# Adafruit_ADG729_Dual_1-to-4_Analog_Switc.net
KiCad netlist of a schematic drawn in EAGLE
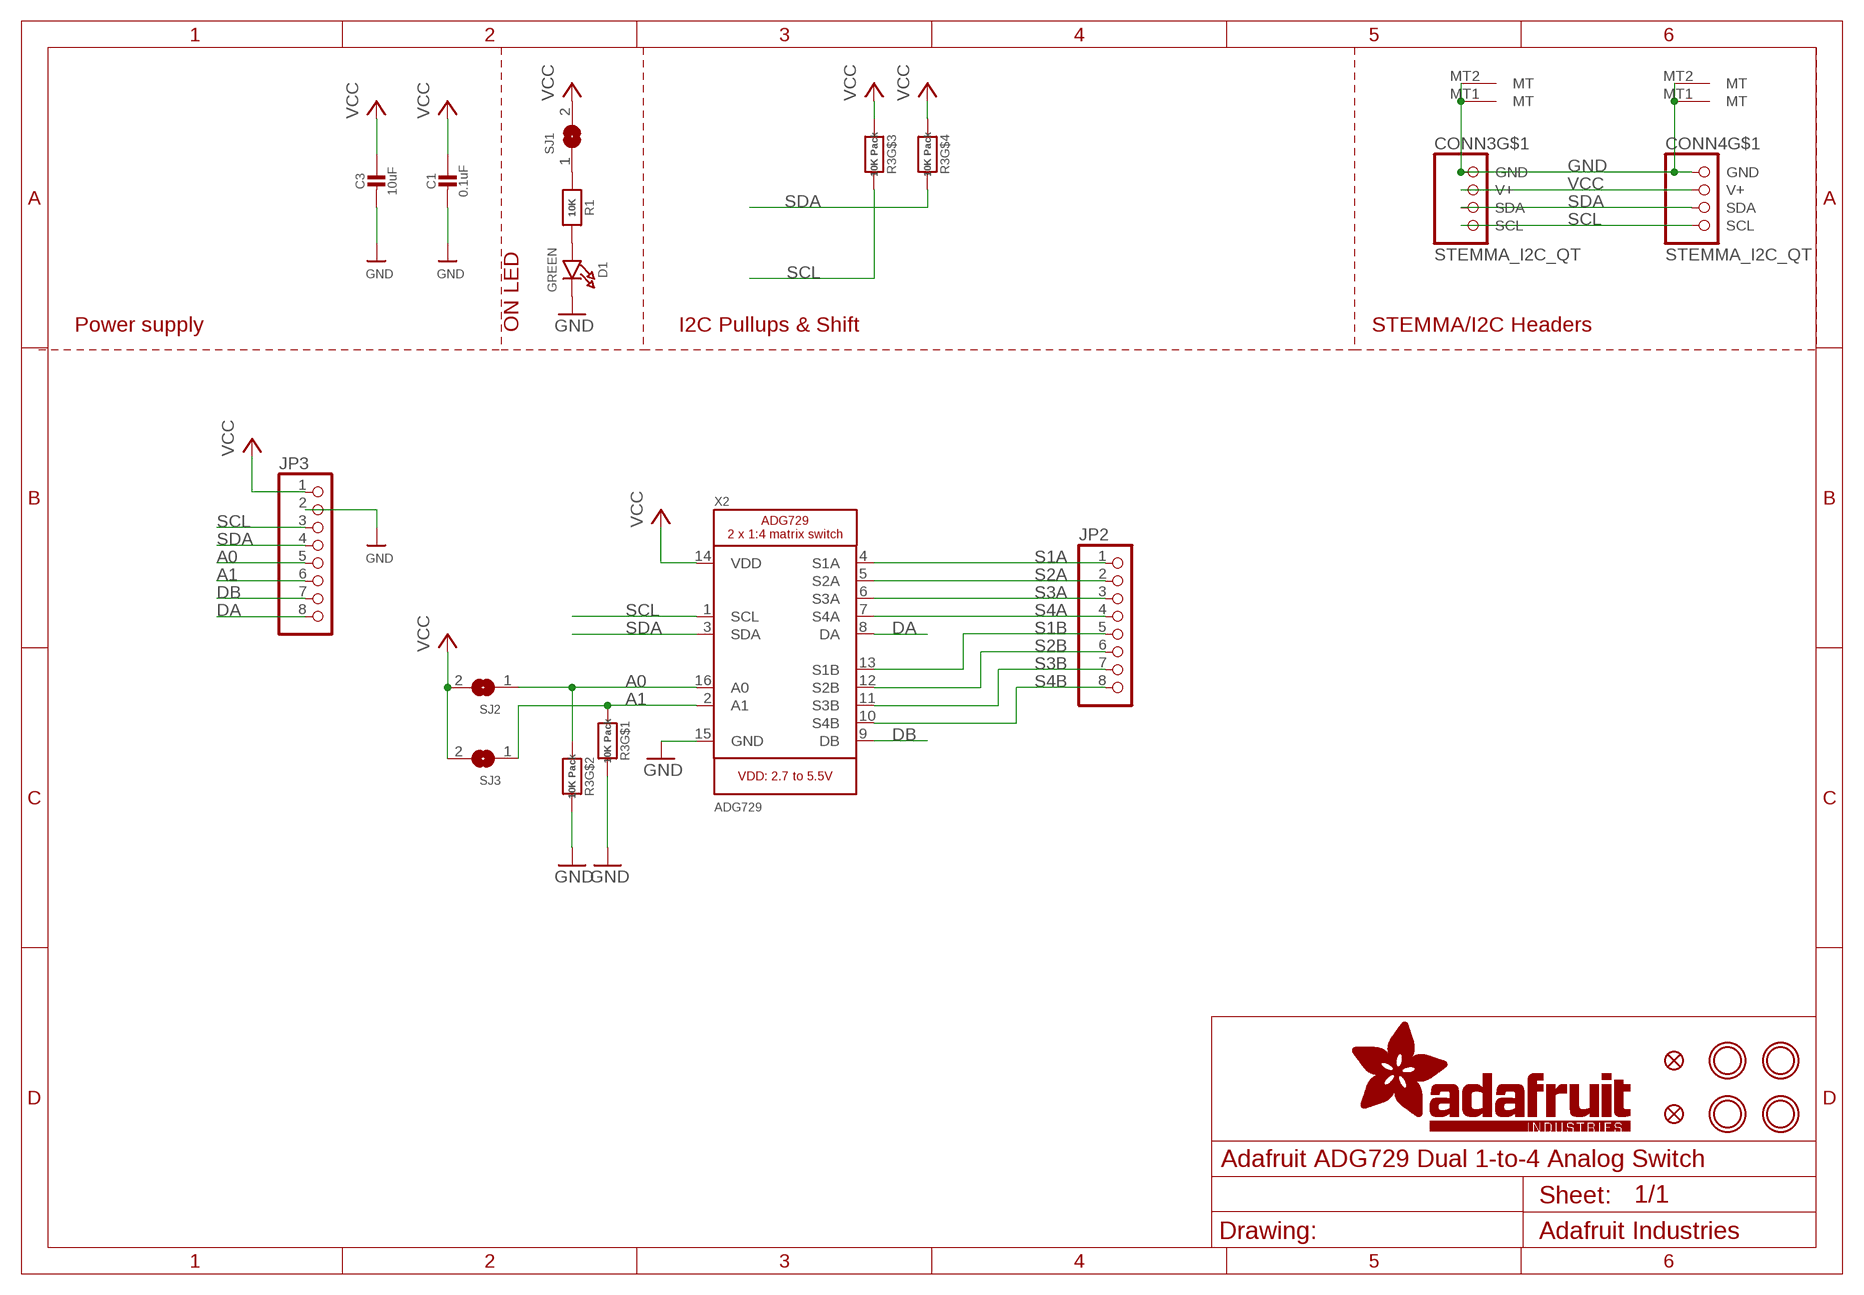
[diagram p0: schematic, sheet 1]

(export (version "E")
  (design (tool "Eeschema 10.0.6"))
  (components
    (comp (ref "C1")
      (value "0.1uF")
      (footprint "eagle-import:0603-NO")
      (libsource (lib "eagle-import") (part "CAP_CERAMIC0603_NO"))
    )
    (comp (ref "C3")
      (value "10uF")
      (footprint "eagle-import:0805-NO")
      (libsource (lib "eagle-import") (part "CAP_CERAMIC0805-NOOUTLINE"))
    )
    (comp (ref "CONN3")
      (value "STEMMA_I2C_QT")
      (footprint "eagle-import:JST_SH4")
      (libsource (lib "eagle-import") (part "STEMMA_I2C_QT"))
    )
    (comp (ref "CONN4")
      (value "STEMMA_I2C_QT")
      (footprint "eagle-import:JST_SH4")
      (libsource (lib "eagle-import") (part "STEMMA_I2C_QT"))
    )
    (comp (ref "D1")
      (value "GREEN")
      (footprint "eagle-import:CHIPLED_0603_NOOUTLINE")
      (libsource (lib "eagle-import") (part "LED0603_NOOUTLINE"))
    )
    (comp (ref "FID3")
      (value "FIDUCIAL_1MM")
      (footprint "eagle-import:FIDUCIAL_1MM")
      (libsource (lib "eagle-import") (part "FIDUCIAL_1MM"))
    )
    (comp (ref "FID4")
      (value "FIDUCIAL_1MM")
      (footprint "eagle-import:FIDUCIAL_1MM")
      (libsource (lib "eagle-import") (part "FIDUCIAL_1MM"))
    )
    (comp (ref "JP2")
      (value "HEADER-1X870MIL")
      (footprint "eagle-import:1X08_ROUND_70")
      (libsource (lib "eagle-import") (part "HEADER-1X870MIL"))
    )
    (comp (ref "JP3")
      (value "HEADER-1X870MIL")
      (footprint "eagle-import:1X08_ROUND_70")
      (libsource (lib "eagle-import") (part "HEADER-1X870MIL"))
    )
    (comp (ref "R1")
      (value "10K")
      (footprint "eagle-import:0603-NO")
      (libsource (lib "eagle-import") (part "RESISTOR_0603_NOOUT"))
    )
    (comp (ref "R3")
      (value "10K Pack")
      (footprint "eagle-import:RESPACK_4X0603")
      (libsource (lib "eagle-import") (part "RESISTOR_4PACK"))
    )
    (comp (ref "SJ1")
      (value "SOLDERJUMPERCLOSED")
      (footprint "eagle-import:SOLDERJUMPER_CLOSEDWIRE")
      (libsource (lib "eagle-import") (part "SOLDERJUMPERCLOSED"))
    )
    (comp (ref "SJ2")
      (value "SOLDERJUMPER")
      (footprint "eagle-import:SOLDERJUMPER_ARROW_NOPASTE")
      (libsource (lib "eagle-import") (part "SOLDERJUMPER"))
    )
    (comp (ref "SJ3")
      (value "SOLDERJUMPER")
      (footprint "eagle-import:SOLDERJUMPER_ARROW_NOPASTE")
      (libsource (lib "eagle-import") (part "SOLDERJUMPER"))
    )
    (comp (ref "U$1")
      (value "MOUNTINGHOLE2.5")
      (footprint "eagle-import:MOUNTINGHOLE_2.5_PLATED")
      (libsource (lib "eagle-import") (part "MOUNTINGHOLE2.5"))
    )
    (comp (ref "U$17")
      (value "MOUNTINGHOLE2.5")
      (footprint "eagle-import:MOUNTINGHOLE_2.5_PLATED")
      (libsource (lib "eagle-import") (part "MOUNTINGHOLE2.5"))
    )
    (comp (ref "U$19")
      (value "MOUNTINGHOLE2.5")
      (footprint "eagle-import:MOUNTINGHOLE_2.5_PLATED")
      (libsource (lib "eagle-import") (part "MOUNTINGHOLE2.5"))
    )
    (comp (ref "U$21")
      (value "MOUNTINGHOLE2.5")
      (footprint "eagle-import:MOUNTINGHOLE_2.5_PLATED")
      (libsource (lib "eagle-import") (part "MOUNTINGHOLE2.5"))
    )
    (comp (ref "X2")
      (value "ADG729")
      (footprint "eagle-import:TSSOP16")
      (libsource (lib "eagle-import") (part "ADG729"))
    )
  )
  (nets
    (net (code "1") (name "/A0") (class "Default")
      (node (ref "JP3") (pin "5") (pinfunction "5_5") (pintype "passive"))
      (node (ref "R3") (pin "2") (pinfunction "1_2") (pintype "passive"))
      (node (ref "SJ2") (pin "1") (pinfunction "1_1") (pintype "passive"))
      (node (ref "X2") (pin "16") (pinfunction "A0_16") (pintype "input"))
    )
    (net (code "2") (name "/A1") (class "Default")
      (node (ref "JP3") (pin "6") (pinfunction "6_6") (pintype "passive"))
      (node (ref "R3") (pin "1") (pinfunction "1_1") (pintype "passive"))
      (node (ref "SJ3") (pin "1") (pinfunction "1_1") (pintype "passive"))
      (node (ref "X2") (pin "2") (pinfunction "A1_2") (pintype "input"))
    )
    (net (code "3") (name "/DA") (class "Default")
      (node (ref "JP3") (pin "8") (pinfunction "8_8") (pintype "passive"))
      (node (ref "X2") (pin "8") (pinfunction "DA_8") (pintype "input"))
    )
    (net (code "4") (name "/DB") (class "Default")
      (node (ref "JP3") (pin "7") (pinfunction "7_7") (pintype "passive"))
      (node (ref "X2") (pin "9") (pinfunction "DB_9") (pintype "input"))
    )
    (net (code "5") (name "/S1A") (class "Default")
      (node (ref "JP2") (pin "1") (pinfunction "1_1") (pintype "passive"))
      (node (ref "X2") (pin "4") (pinfunction "S1A_4") (pintype "input"))
    )
    (net (code "6") (name "/S1B") (class "Default")
      (node (ref "JP2") (pin "5") (pinfunction "5_5") (pintype "passive"))
      (node (ref "X2") (pin "13") (pinfunction "S1B_13") (pintype "input"))
    )
    (net (code "7") (name "/S2A") (class "Default")
      (node (ref "JP2") (pin "2") (pinfunction "2_2") (pintype "passive"))
      (node (ref "X2") (pin "5") (pinfunction "S2A_5") (pintype "input"))
    )
    (net (code "8") (name "/S2B") (class "Default")
      (node (ref "JP2") (pin "6") (pinfunction "6_6") (pintype "passive"))
      (node (ref "X2") (pin "12") (pinfunction "S2B_12") (pintype "input"))
    )
    (net (code "9") (name "/S3A") (class "Default")
      (node (ref "JP2") (pin "3") (pinfunction "3_3") (pintype "passive"))
      (node (ref "X2") (pin "6") (pinfunction "S3A_6") (pintype "input"))
    )
    (net (code "10") (name "/S3B") (class "Default")
      (node (ref "JP2") (pin "7") (pinfunction "7_7") (pintype "passive"))
      (node (ref "X2") (pin "11") (pinfunction "S3B_11") (pintype "input"))
    )
    (net (code "11") (name "/S4A") (class "Default")
      (node (ref "JP2") (pin "4") (pinfunction "4_4") (pintype "passive"))
      (node (ref "X2") (pin "7") (pinfunction "S4A_7") (pintype "input"))
    )
    (net (code "12") (name "/S4B") (class "Default")
      (node (ref "JP2") (pin "8") (pinfunction "8_8") (pintype "passive"))
      (node (ref "X2") (pin "10") (pinfunction "S4B_10") (pintype "input"))
    )
    (net (code "13") (name "/SCL") (class "Default")
      (node (ref "CONN3") (pin "4") (pinfunction "SCL_4") (pintype "passive"))
      (node (ref "CONN4") (pin "4") (pinfunction "SCL_4") (pintype "passive"))
      (node (ref "JP3") (pin "3") (pinfunction "3_3") (pintype "passive"))
      (node (ref "R3") (pin "6") (pinfunction "2_6") (pintype "passive"))
      (node (ref "X2") (pin "1") (pinfunction "SCL_1") (pintype "bidirectional"))
    )
    (net (code "14") (name "/SDA") (class "Default")
      (node (ref "CONN3") (pin "3") (pinfunction "SDA_3") (pintype "passive"))
      (node (ref "CONN4") (pin "3") (pinfunction "SDA_3") (pintype "passive"))
      (node (ref "JP3") (pin "4") (pinfunction "4_4") (pintype "passive"))
      (node (ref "R3") (pin "5") (pinfunction "2_5") (pintype "passive"))
      (node (ref "X2") (pin "3") (pinfunction "SDA_3") (pintype "bidirectional"))
    )
    (net (code "15") (name "GND") (class "Default")
      (node (ref "C1") (pin "2") (pinfunction "2_2") (pintype "passive"))
      (node (ref "C3") (pin "2") (pinfunction "2_2") (pintype "passive"))
      (node (ref "CONN3") (pin "1") (pinfunction "GND_1") (pintype "passive"))
      (node (ref "CONN3") (pin "MT1") (pinfunction "MT_MT1") (pintype "bidirectional"))
      (node (ref "CONN3") (pin "MT2") (pinfunction "MT_MT2") (pintype "bidirectional"))
      (node (ref "CONN4") (pin "1") (pinfunction "GND_1") (pintype "passive"))
      (node (ref "CONN4") (pin "MT1") (pinfunction "MT_MT1") (pintype "bidirectional"))
      (node (ref "CONN4") (pin "MT2") (pinfunction "MT_MT2") (pintype "bidirectional"))
      (node (ref "D1") (pin "C") (pinfunction "C_C") (pintype "passive"))
      (node (ref "JP3") (pin "2") (pinfunction "2_2") (pintype "passive"))
      (node (ref "R3") (pin "7") (pinfunction "2_7") (pintype "passive"))
      (node (ref "R3") (pin "8") (pinfunction "2_8") (pintype "passive"))
      (node (ref "X2") (pin "15") (pinfunction "GND_15") (pintype "power_in"))
    )
    (net (code "16") (name "Net-(D1-PadA)") (class "Default")
      (node (ref "D1") (pin "A") (pinfunction "A_A") (pintype "passive"))
      (node (ref "R1") (pin "2") (pinfunction "2_2") (pintype "passive"))
    )
    (net (code "17") (name "Net-(R1-Pad1)") (class "Default")
      (node (ref "R1") (pin "1") (pinfunction "1_1") (pintype "passive"))
      (node (ref "SJ1") (pin "1") (pinfunction "1_1") (pintype "passive"))
    )
    (net (code "18") (name "VCC") (class "Default")
      (node (ref "C1") (pin "1") (pinfunction "1_1") (pintype "passive"))
      (node (ref "C3") (pin "1") (pinfunction "1_1") (pintype "passive"))
      (node (ref "CONN3") (pin "2") (pinfunction "V+_2") (pintype "passive"))
      (node (ref "CONN4") (pin "2") (pinfunction "V+_2") (pintype "passive"))
      (node (ref "JP3") (pin "1") (pinfunction "1_1") (pintype "passive"))
      (node (ref "R3") (pin "3") (pinfunction "1_3") (pintype "passive"))
      (node (ref "R3") (pin "4") (pinfunction "1_4") (pintype "passive"))
      (node (ref "SJ1") (pin "2") (pinfunction "2_2") (pintype "passive"))
      (node (ref "SJ2") (pin "2") (pinfunction "2_2") (pintype "passive"))
      (node (ref "SJ3") (pin "2") (pinfunction "2_2") (pintype "passive"))
      (node (ref "X2") (pin "14") (pinfunction "VDD_14") (pintype "power_in"))
    )
  )
)
